# SCH-11-Out_Going_Connectors.net
KiCad netlist of a schematic drawn in Altium Designer
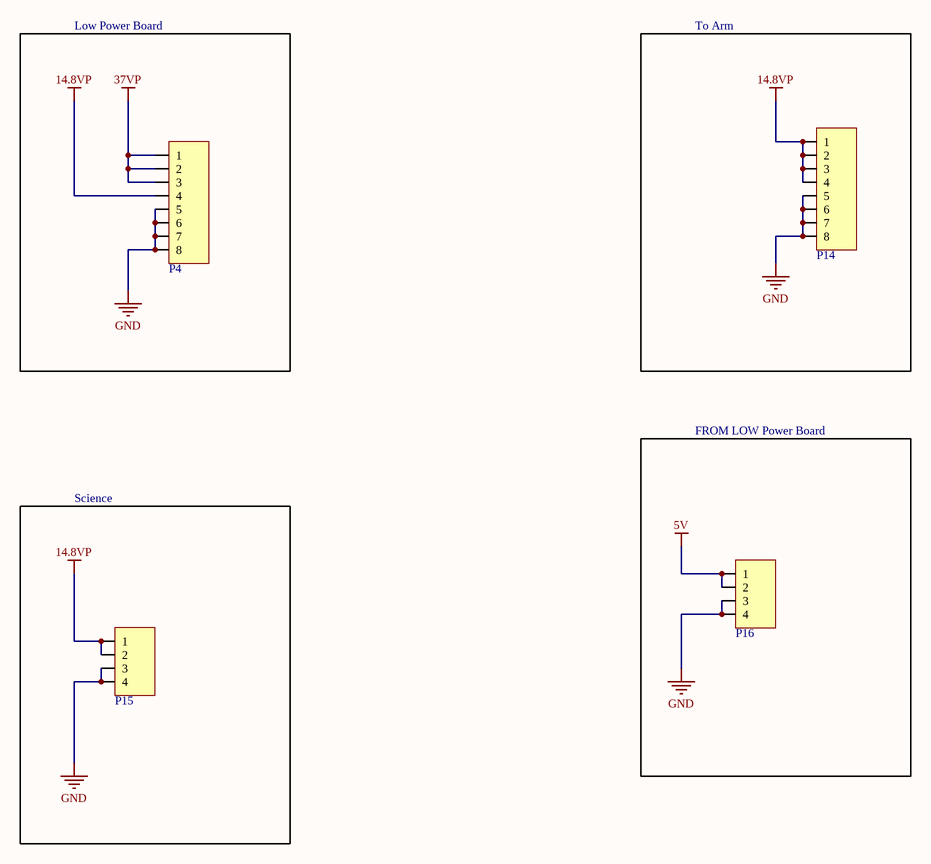
[diagram p0: SCH-11-Out Going Connectors.SchDoc]

(export (version "E")
  (design (tool "Eeschema 10.0.6"))
  (components
    (comp (ref "P4")
      (value "Mini-Fit Jr 8 Pos")
      (footprint "Molex Mini-Fit Jr 0039281083")
      (libsource (lib "RSX_Connectors") (part "Molex Mini-Fit Jr 8pos Vert"))
    )
    (comp (ref "P14")
      (value "Mini-Fit Jr 8 Pos RA")
      (footprint "MOLEX 172065-0208")
      (libsource (lib "RSX_Connectors") (part "Molex Mega-Fit 8pos Vert"))
    )
    (comp (ref "P15")
      (value "Mini-Fit Jr 4 Pos")
      (footprint "MOLEX 0039281043")
      (libsource (lib "RSX_Connectors") (part "Molex 0039281043"))
    )
    (comp (ref "P16")
      (value "Mini-Fit Jr 4 Pos")
      (footprint "MOLEX 0039281043")
      (libsource (lib "RSX_Connectors") (part "Molex 0039281043"))
    )
  )
  (nets
    (net (code "1") (name "5V") (class "Default")
      (node (ref "P16") (pin "1") (pinfunction "1_1") (pintype "passive"))
      (node (ref "P16") (pin "2") (pinfunction "2_2") (pintype "passive"))
    )
    (net (code "2") (name "14.8VP") (class "Default")
      (node (ref "P14") (pin "1") (pinfunction "1_1") (pintype "passive"))
      (node (ref "P14") (pin "2") (pinfunction "2_2") (pintype "passive"))
      (node (ref "P14") (pin "3") (pinfunction "3_3") (pintype "passive"))
      (node (ref "P14") (pin "4") (pinfunction "4_4") (pintype "passive"))
      (node (ref "P15") (pin "1") (pinfunction "1_1") (pintype "passive"))
      (node (ref "P15") (pin "2") (pinfunction "2_2") (pintype "passive"))
      (node (ref "P4") (pin "4") (pinfunction "4_4") (pintype "passive"))
    )
    (net (code "3") (name "37VP") (class "Default")
      (node (ref "P4") (pin "1") (pinfunction "1_1") (pintype "passive"))
      (node (ref "P4") (pin "2") (pinfunction "2_2") (pintype "passive"))
      (node (ref "P4") (pin "3") (pinfunction "3_3") (pintype "passive"))
    )
    (net (code "4") (name "GND") (class "Default")
      (node (ref "P14") (pin "5") (pinfunction "5_5") (pintype "passive"))
      (node (ref "P14") (pin "6") (pinfunction "6_6") (pintype "passive"))
      (node (ref "P14") (pin "7") (pinfunction "7_7") (pintype "passive"))
      (node (ref "P14") (pin "8") (pinfunction "8_8") (pintype "passive"))
      (node (ref "P15") (pin "3") (pinfunction "3_3") (pintype "passive"))
      (node (ref "P15") (pin "4") (pinfunction "4_4") (pintype "passive"))
      (node (ref "P16") (pin "3") (pinfunction "3_3") (pintype "passive"))
      (node (ref "P16") (pin "4") (pinfunction "4_4") (pintype "passive"))
      (node (ref "P4") (pin "5") (pinfunction "5_5") (pintype "passive"))
      (node (ref "P4") (pin "6") (pinfunction "6_6") (pintype "passive"))
      (node (ref "P4") (pin "7") (pinfunction "7_7") (pintype "passive"))
      (node (ref "P4") (pin "8") (pinfunction "8_8") (pintype "passive"))
    )
  )
)
